# cpu.net
KiCad netlist of a schematic drawn in EAGLE
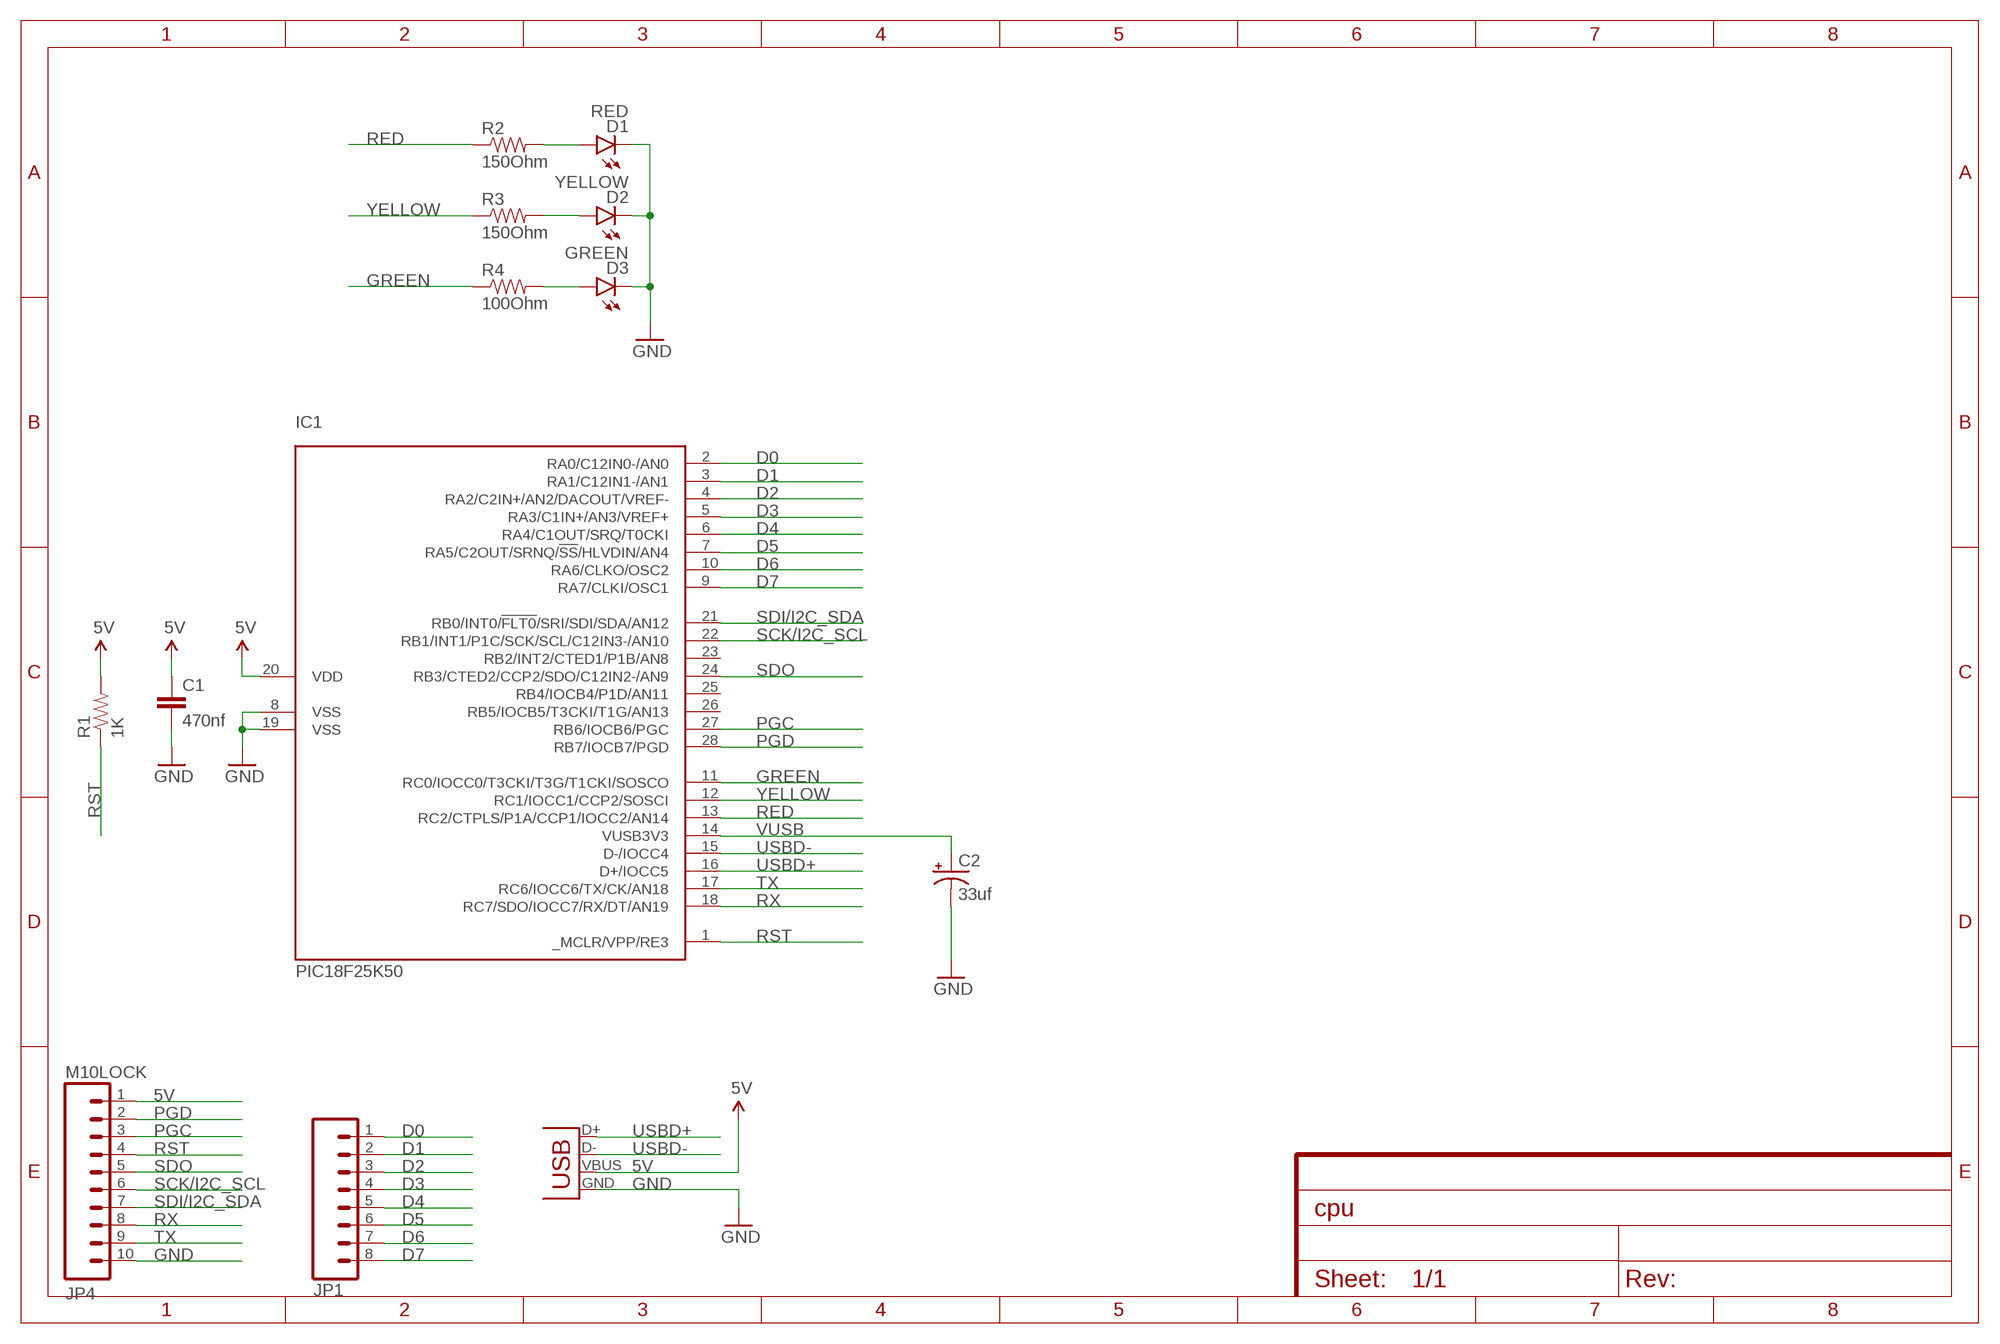
[diagram p0: schematic, sheet 1]

(export (version "E")
  (design (tool "Eeschema 10.0.6"))
  (components
    (comp (ref "C1")
      (value "470nf")
      (footprint "eagle-import:0805")
      (libsource (lib "eagle-import") (part "CAP0805"))
    )
    (comp (ref "C2")
      (value "33uf")
      (footprint "eagle-import:PANASONIC_D")
      (libsource (lib "eagle-import") (part "47UF-50V-20%(ELECT)"))
    )
    (comp (ref "D1")
      (value "RED")
      (footprint "eagle-import:LED-0603")
      (libsource (lib "eagle-import") (part "LED-RED0603"))
    )
    (comp (ref "D2")
      (value "YELLOW")
      (footprint "eagle-import:LED-0603")
      (libsource (lib "eagle-import") (part "LED-YELLOW0603"))
    )
    (comp (ref "D3")
      (value "GREEN")
      (footprint "eagle-import:LED-0603")
      (libsource (lib "eagle-import") (part "LED-GREEN0603"))
    )
    (comp (ref "IC1")
      (value "PIC18F25K50")
      (footprint "eagle-import:SO-28W")
      (libsource (lib "eagle-import") (part "PIC18F25K50"))
    )
    (comp (ref "JP1")
      (value "M08LOCK")
      (footprint "eagle-import:1X08_LOCK")
      (libsource (lib "eagle-import") (part "M08LOCK"))
    )
    (comp (ref "JP3")
      (value "USBSMD")
      (footprint "eagle-import:USB-MINIB")
      (libsource (lib "eagle-import") (part "USBSMD"))
    )
    (comp (ref "JP4")
      (value "M10LOCK")
      (footprint "eagle-import:1X10_LOCK")
      (libsource (lib "eagle-import") (part "M10LOCK"))
    )
    (comp (ref "R1")
      (value "1K")
      (footprint "eagle-import:0603-RES")
      (libsource (lib "eagle-import") (part "1KOHM1/10W1%(0603)"))
    )
    (comp (ref "R2")
      (value "150Ohm")
      (footprint "eagle-import:0402-RES")
      (libsource (lib "eagle-import") (part "RESISTOR0402-RES"))
    )
    (comp (ref "R3")
      (value "150Ohm")
      (footprint "eagle-import:0402-RES")
      (libsource (lib "eagle-import") (part "RESISTOR0402-RES"))
    )
    (comp (ref "R4")
      (value "100Ohm")
      (footprint "eagle-import:0402-RES")
      (libsource (lib "eagle-import") (part "RESISTOR0402-RES"))
    )
  )
  (nets
    (net (code "1") (name "/D0") (class "Default")
      (node (ref "IC1") (pin "2") (pinfunction "RA0/C12IN0-/AN0_2") (pintype "bidirectional"))
      (node (ref "JP1") (pin "1") (pinfunction "1_1") (pintype "passive"))
    )
    (net (code "2") (name "/D1") (class "Default")
      (node (ref "IC1") (pin "3") (pinfunction "RA1/C12IN1-/AN1_3") (pintype "bidirectional"))
      (node (ref "JP1") (pin "2") (pinfunction "2_2") (pintype "passive"))
    )
    (net (code "3") (name "/D2") (class "Default")
      (node (ref "IC1") (pin "4") (pinfunction "RA2/C2IN+/AN2/DACOUT/VREF-_4") (pintype "bidirectional"))
      (node (ref "JP1") (pin "3") (pinfunction "3_3") (pintype "passive"))
    )
    (net (code "4") (name "/D3") (class "Default")
      (node (ref "IC1") (pin "5") (pinfunction "RA3/C1IN+/AN3/VREF+_5") (pintype "bidirectional"))
      (node (ref "JP1") (pin "4") (pinfunction "4_4") (pintype "passive"))
    )
    (net (code "5") (name "/D4") (class "Default")
      (node (ref "IC1") (pin "6") (pinfunction "RA4/C1OUT/SRQ/T0CKI_6") (pintype "bidirectional"))
      (node (ref "JP1") (pin "5") (pinfunction "5_5") (pintype "passive"))
    )
    (net (code "6") (name "/D5") (class "Default")
      (node (ref "IC1") (pin "7") (pinfunction "RA5/C2OUT/SRNQ/~{SS}/HLVDIN/AN4_7") (pintype "bidirectional"))
      (node (ref "JP1") (pin "6") (pinfunction "6_6") (pintype "passive"))
    )
    (net (code "7") (name "/D6") (class "Default")
      (node (ref "IC1") (pin "10") (pinfunction "RA6/CLKO/OSC2_10") (pintype "bidirectional"))
      (node (ref "JP1") (pin "7") (pinfunction "7_7") (pintype "passive"))
    )
    (net (code "8") (name "/D7") (class "Default")
      (node (ref "IC1") (pin "9") (pinfunction "RA7/CLKI/OSC1_9") (pintype "bidirectional"))
      (node (ref "JP1") (pin "8") (pinfunction "8_8") (pintype "passive"))
    )
    (net (code "9") (name "/GREEN") (class "Default")
      (node (ref "IC1") (pin "11") (pinfunction "RC0/IOCC0/T3CKI/T3G/T1CKI/SOSCO_11") (pintype "bidirectional"))
      (node (ref "R4") (pin "1") (pinfunction "1_1") (pintype "passive"))
    )
    (net (code "10") (name "/PGC") (class "Default")
      (node (ref "IC1") (pin "27") (pinfunction "RB6/IOCB6/PGC_27") (pintype "bidirectional"))
      (node (ref "JP4") (pin "3") (pinfunction "3_3") (pintype "passive"))
    )
    (net (code "11") (name "/PGD") (class "Default")
      (node (ref "IC1") (pin "28") (pinfunction "RB7/IOCB7/PGD_28") (pintype "bidirectional"))
      (node (ref "JP4") (pin "2") (pinfunction "2_2") (pintype "passive"))
    )
    (net (code "12") (name "/RED") (class "Default")
      (node (ref "IC1") (pin "13") (pinfunction "RC2/CTPLS/P1A/CCP1/IOCC2/AN14_13") (pintype "bidirectional"))
      (node (ref "R2") (pin "1") (pinfunction "1_1") (pintype "passive"))
    )
    (net (code "13") (name "/RST") (class "Default")
      (node (ref "IC1") (pin "1") (pinfunction "_MCLR/VPP/RE3_1") (pintype "input"))
      (node (ref "JP4") (pin "4") (pinfunction "4_4") (pintype "passive"))
      (node (ref "R1") (pin "1") (pinfunction "1_1") (pintype "passive"))
    )
    (net (code "14") (name "/RX") (class "Default")
      (node (ref "IC1") (pin "18") (pinfunction "RC7/SDO/IOCC7/RX/DT/AN19_18") (pintype "bidirectional"))
      (node (ref "JP4") (pin "8") (pinfunction "8_8") (pintype "passive"))
    )
    (net (code "15") (name "/SCK{slash}I2C_SCL") (class "Default")
      (node (ref "IC1") (pin "22") (pinfunction "RB1/INT1/P1C/SCK/SCL/C12IN3-/AN10_22") (pintype "bidirectional"))
      (node (ref "JP4") (pin "6") (pinfunction "6_6") (pintype "passive"))
    )
    (net (code "16") (name "/SDI{slash}I2C_SDA") (class "Default")
      (node (ref "IC1") (pin "21") (pinfunction "RB0/INT0/~{FLT0}/SRI/SDI/SDA/AN12_21") (pintype "bidirectional"))
      (node (ref "JP4") (pin "7") (pinfunction "7_7") (pintype "passive"))
    )
    (net (code "17") (name "/SDO") (class "Default")
      (node (ref "IC1") (pin "24") (pinfunction "RB3/CTED2/CCP2/SDO/C12IN2-/AN9_24") (pintype "bidirectional"))
      (node (ref "JP4") (pin "5") (pinfunction "5_5") (pintype "passive"))
    )
    (net (code "18") (name "/TX") (class "Default")
      (node (ref "IC1") (pin "17") (pinfunction "RC6/IOCC6/TX/CK/AN18_17") (pintype "bidirectional"))
      (node (ref "JP4") (pin "9") (pinfunction "9_9") (pintype "passive"))
    )
    (net (code "19") (name "/USBD+") (class "Default")
      (node (ref "IC1") (pin "16") (pinfunction "D+/IOCC5_16") (pintype "bidirectional"))
      (node (ref "JP3") (pin "D+") (pinfunction "D+_D+") (pintype "bidirectional"))
    )
    (net (code "20") (name "/USBD-") (class "Default")
      (node (ref "IC1") (pin "15") (pinfunction "D-/IOCC4_15") (pintype "bidirectional"))
      (node (ref "JP3") (pin "D-") (pinfunction "D-_D-") (pintype "bidirectional"))
    )
    (net (code "21") (name "/VUSB") (class "Default")
      (node (ref "C2") (pin "+") (pinfunction "+_+") (pintype "passive"))
      (node (ref "IC1") (pin "14") (pinfunction "VUSB3V3_14") (pintype "bidirectional"))
    )
    (net (code "22") (name "/YELLOW") (class "Default")
      (node (ref "IC1") (pin "12") (pinfunction "RC1/IOCC1/CCP2/SOSCI_12") (pintype "bidirectional"))
      (node (ref "R3") (pin "1") (pinfunction "1_1") (pintype "passive"))
    )
    (net (code "23") (name "5V") (class "Default")
      (node (ref "C1") (pin "1") (pinfunction "1_1") (pintype "passive"))
      (node (ref "IC1") (pin "20") (pinfunction "VDD_20") (pintype "power_in"))
      (node (ref "JP3") (pin "VBUS") (pinfunction "VBUS_VBUS") (pintype "bidirectional"))
      (node (ref "JP4") (pin "1") (pinfunction "1_1") (pintype "passive"))
      (node (ref "R1") (pin "2") (pinfunction "2_2") (pintype "passive"))
    )
    (net (code "24") (name "GND") (class "Default")
      (node (ref "C1") (pin "2") (pinfunction "2_2") (pintype "passive"))
      (node (ref "C2") (pin "-") (pinfunction "-_-") (pintype "passive"))
      (node (ref "D1") (pin "C") (pinfunction "C_C") (pintype "passive"))
      (node (ref "D2") (pin "C") (pinfunction "C_C") (pintype "passive"))
      (node (ref "D3") (pin "C") (pinfunction "C_C") (pintype "passive"))
      (node (ref "IC1") (pin "19") (pinfunction "VSS_19") (pintype "power_in"))
      (node (ref "IC1") (pin "8") (pinfunction "VSS_8") (pintype "power_in"))
      (node (ref "JP3") (pin "GND") (pinfunction "GND_GND") (pintype "bidirectional"))
      (node (ref "JP4") (pin "10") (pinfunction "10_10") (pintype "passive"))
    )
    (net (code "25") (name "Net-(D1-PadA)") (class "Default")
      (node (ref "D1") (pin "A") (pinfunction "A_A") (pintype "passive"))
      (node (ref "R2") (pin "2") (pinfunction "2_2") (pintype "passive"))
    )
    (net (code "26") (name "Net-(D2-PadA)") (class "Default")
      (node (ref "D2") (pin "A") (pinfunction "A_A") (pintype "passive"))
      (node (ref "R3") (pin "2") (pinfunction "2_2") (pintype "passive"))
    )
    (net (code "27") (name "Net-(D3-PadA)") (class "Default")
      (node (ref "D3") (pin "A") (pinfunction "A_A") (pintype "passive"))
      (node (ref "R4") (pin "2") (pinfunction "2_2") (pintype "passive"))
    )
    (net (code "28") (name "unconnected-(IC1-RB2{slash}INT2{slash}CTED1{slash}P1B{slash}AN8-Pad23)") (class "Default")
      (node (ref "IC1") (pin "23") (pinfunction "RB2/INT2/CTED1/P1B/AN8_23") (pintype "bidirectional"))
    )
    (net (code "29") (name "unconnected-(IC1-RB4{slash}IOCB4{slash}P1D{slash}AN11-Pad25)") (class "Default")
      (node (ref "IC1") (pin "25") (pinfunction "RB4/IOCB4/P1D/AN11_25") (pintype "bidirectional"))
    )
    (net (code "30") (name "unconnected-(IC1-RB5{slash}IOCB5{slash}T3CKI{slash}T1G{slash}AN13-Pad26)") (class "Default")
      (node (ref "IC1") (pin "26") (pinfunction "RB5/IOCB5/T3CKI/T1G/AN13_26") (pintype "bidirectional"))
    )
  )
)
